# MCU_LDO.net
KiCad netlist of a schematic drawn in Altium Designer
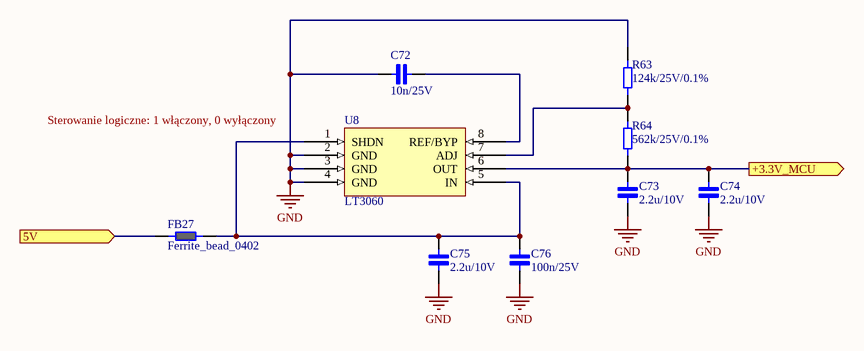
[diagram p0: MCU_LDO.SchDoc]

(export (version "E")
  (design (tool "Eeschema 10.0.6"))
  (components
    (comp (ref "C72")
      (value "10n/25V")
      (footprint "Cap_0402")
      (description "Ceramic Capacitor 10n / 0402 / 25V / ±5%, Wurth Elektronik MLCC")
      (libsource (lib "Cubesat_lib") (part "Cap_0402_10n"))
    )
    (comp (ref "C73")
      (value "2.2u/10V")
      (footprint "Cap_0402")
      (description "Ceramic Capacitor 2.2uF / 0402 / 10V / ±5%, Wurth Elektronik MLCC")
      (libsource (lib "Cubesat_lib") (part "Cap_0402_2.2u"))
    )
    (comp (ref "C74")
      (value "2.2u/10V")
      (footprint "Cap_0402")
      (description "Ceramic Capacitor 2.2uF / 0402 / 10V / ±5%, Wurth Elektronik MLCC")
      (libsource (lib "Cubesat_lib") (part "Cap_0402_2.2u"))
    )
    (comp (ref "C75")
      (value "2.2u/10V")
      (footprint "Cap_0402")
      (description "Ceramic Capacitor 2.2uF / 0402 / 10V / ±5%, Wurth Elektronik MLCC")
      (libsource (lib "Cubesat_lib") (part "Cap_0402_2.2u"))
    )
    (comp (ref "C76")
      (value "100n/25V")
      (footprint "Cap_0402")
      (description "Ceramic Capacitor 100n / 0402 / 25V / ±5%, Wurth Elektronik MLCC")
      (libsource (lib "Cubesat_lib") (part "Cap_0402_100n"))
    )
    (comp (ref "FB27")
      (value "Ferrite_bead_0402")
      (footprint "FERRITE_0402")
      (description "Ferrite bead, wurth 74269241102")
      (libsource (lib "Cubesat_lib") (part "Ferrite_bead_0402"))
    )
    (comp (ref "R63")
      (value "124k/25V/0.1%")
      (footprint "RES_0402")
      (description "Vishay, thin film resistor 124k/25V/0.1%")
      (libsource (lib "Cubesat_lib") (part "Res_0402_124k"))
    )
    (comp (ref "R64")
      (value "562k/25V/0.1%")
      (footprint "RES_0402")
      (description "Vishay, thin film resistor 562k/25V/0.1%")
      (libsource (lib "Cubesat_lib") (part "Res_0402_562k"))
    )
    (comp (ref "U8")
      (value "LT3060")
      (footprint "TS8")
      (description "45V VIN, Micropower,\r\nLow Noise, 100mA Low\r\nDropout, Linear Regulator")
      (libsource (lib "Cubesat_lib") (part "Lt3060"))
    )
  )
  (nets
    (net (code "1") (name "/+3.3V_MCU") (class "Default")
      (node (ref "C73") (pin "2") (pinfunction "2_2") (pintype "passive"))
      (node (ref "C74") (pin "2") (pinfunction "2_2") (pintype "passive"))
      (node (ref "R64") (pin "1") (pinfunction "1_1") (pintype "passive"))
      (node (ref "U8") (pin "6") (pinfunction "OUT_6") (pintype "input"))
    )
    (net (code "2") (name "/5V") (class "Default")
      (node (ref "FB27") (pin "1") (pinfunction "1_1") (pintype "passive"))
    )
    (net (code "3") (name "GND") (class "Default")
      (node (ref "C72") (pin "1") (pinfunction "1_1") (pintype "passive"))
      (node (ref "C73") (pin "1") (pinfunction "1_1") (pintype "passive"))
      (node (ref "C74") (pin "1") (pinfunction "1_1") (pintype "passive"))
      (node (ref "C75") (pin "1") (pinfunction "1_1") (pintype "passive"))
      (node (ref "C76") (pin "1") (pinfunction "1_1") (pintype "passive"))
      (node (ref "R63") (pin "2") (pinfunction "2_2") (pintype "passive"))
      (node (ref "U8") (pin "2") (pinfunction "GND_2") (pintype "input"))
      (node (ref "U8") (pin "3") (pinfunction "GND_3") (pintype "input"))
      (node (ref "U8") (pin "4") (pinfunction "GND_4") (pintype "input"))
    )
    (net (code "4") (name "Net-(U8-ADJ)") (class "Default")
      (node (ref "R63") (pin "1") (pinfunction "1_1") (pintype "passive"))
      (node (ref "R64") (pin "2") (pinfunction "2_2") (pintype "passive"))
      (node (ref "U8") (pin "7") (pinfunction "ADJ_7") (pintype "input"))
    )
    (net (code "5") (name "Net-(U8-IN)") (class "Default")
      (node (ref "C75") (pin "2") (pinfunction "2_2") (pintype "passive"))
      (node (ref "C76") (pin "2") (pinfunction "2_2") (pintype "passive"))
      (node (ref "FB27") (pin "2") (pinfunction "2_2") (pintype "passive"))
      (node (ref "U8") (pin "1") (pinfunction "SHDN_1") (pintype "input"))
      (node (ref "U8") (pin "5") (pinfunction "IN_5") (pintype "input"))
    )
    (net (code "6") (name "Net-(U8-REF{slash}BYP)") (class "Default")
      (node (ref "C72") (pin "2") (pinfunction "2_2") (pintype "passive"))
      (node (ref "U8") (pin "8") (pinfunction "REF/BYP_8") (pintype "input"))
    )
  )
)
